# power.net
KiCad netlist of a schematic drawn in Altium Designer
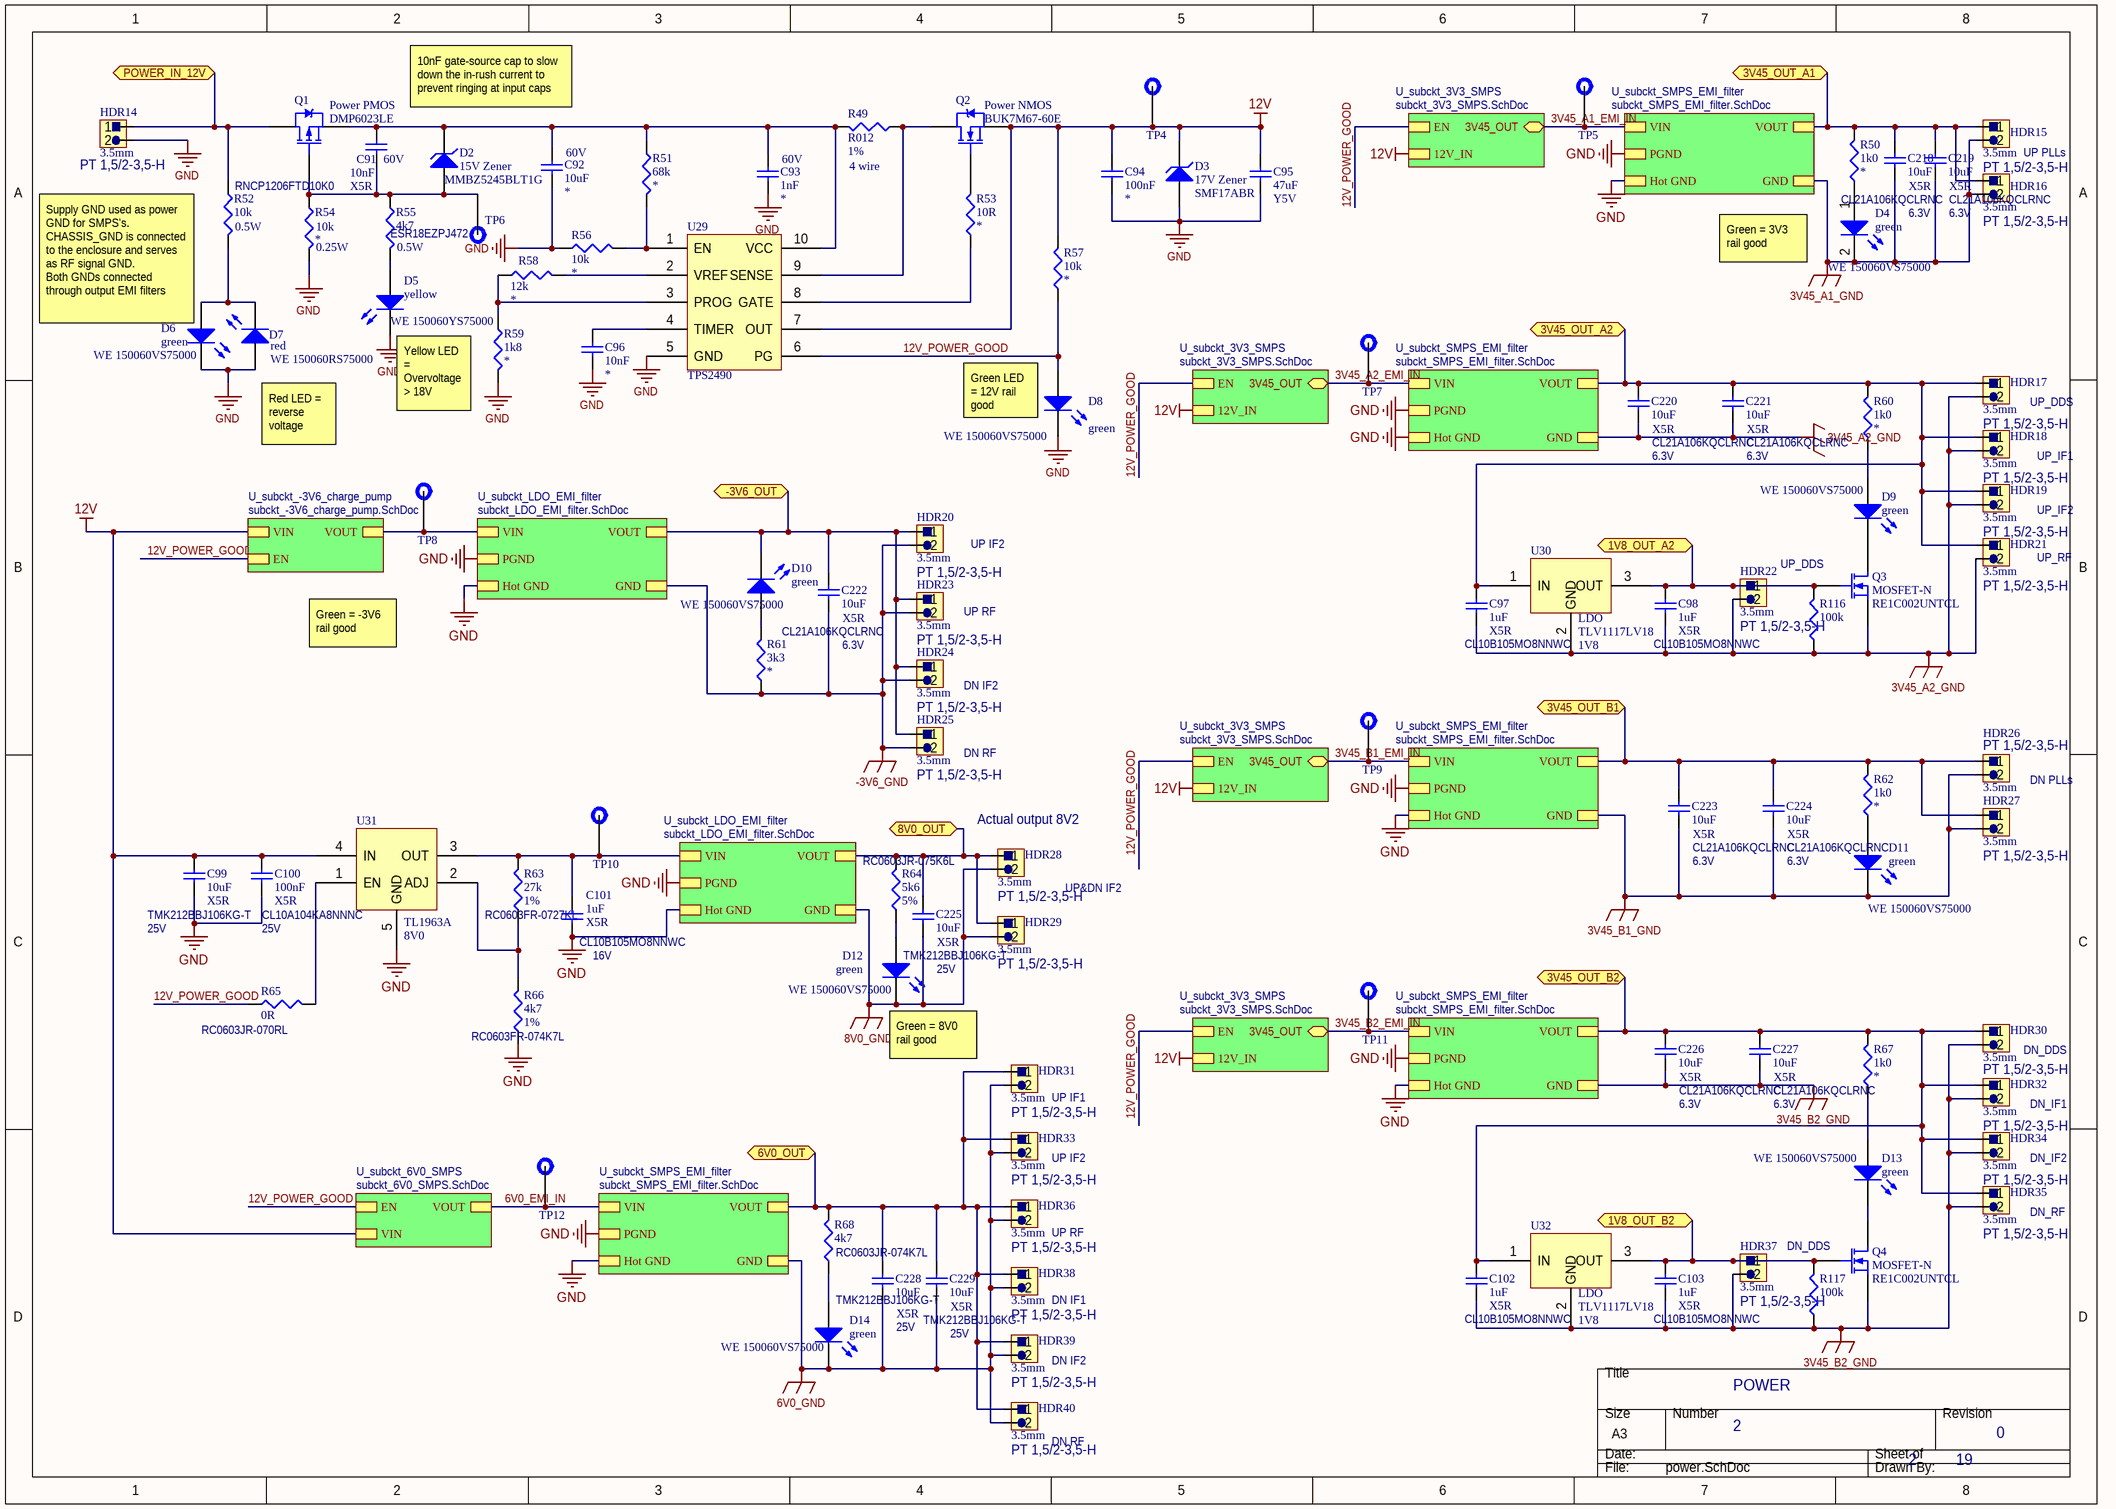
[diagram p0: power.SchDoc]

(export (version "E")
  (design (tool "Eeschema 10.0.6"))
  (components
    (comp (ref "C91")
      (value "60V")
      (footprint "TBD")
      (description "Capacitor")
      (fields (field (name "ALTIUM_VALUE") "10nF") (field (name "DIELECTRIC") "X5R"))
      (libsource (lib "lib_basic") (part "Capacitor"))
    )
    (comp (ref "C92")
      (value "60V")
      (footprint "TBD")
      (description "Capacitor")
      (fields (field (name "ALTIUM_VALUE") "10uF") (field (name "DIELECTRIC") "*"))
      (libsource (lib "lib_basic") (part "Capacitor"))
    )
    (comp (ref "C93")
      (value "60V")
      (footprint "TBD")
      (description "Capacitor")
      (fields (field (name "ALTIUM_VALUE") "1nF") (field (name "DIELECTRIC") "*"))
      (libsource (lib "lib_basic") (part "Capacitor"))
    )
    (comp (ref "C94")
      (value "100nF")
      (footprint "TBD")
      (description "Capacitor")
      (fields (field (name "DIELECTRIC") "*"))
      (libsource (lib "lib_basic") (part "Capacitor"))
    )
    (comp (ref "C95")
      (value "47uF")
      (footprint "TBD")
      (description "Capacitor")
      (fields (field (name "DIELECTRIC") "Y5V"))
      (libsource (lib "lib_basic") (part "Capacitor"))
    )
    (comp (ref "C96")
      (value "10nF")
      (footprint "TBD")
      (description "Capacitor")
      (fields (field (name "DIELECTRIC") "*"))
      (libsource (lib "lib_basic") (part "Capacitor"))
    )
    (comp (ref "C97")
      (value "1uF")
      (footprint "CAP0603")
      (description "Capacitor")
      (fields (field (name "DIELECTRIC") "X5R") (field (name "MODEL") "CL10B105MO8NNWC"))
      (libsource (lib "lib_basic") (part "Capacitor"))
    )
    (comp (ref "C98")
      (value "1uF")
      (footprint "CAP0603")
      (description "Capacitor")
      (fields (field (name "DIELECTRIC") "X5R") (field (name "MODEL") "CL10B105MO8NNWC"))
      (libsource (lib "lib_basic") (part "Capacitor"))
    )
    (comp (ref "C99")
      (value "10uF")
      (footprint "lib_basic:CAP0805")
      (description "Capacitor")
      (fields
        (field (name "DIELECTRIC") "X5R")
        (field (name "MODEL") "TMK212BBJ106KG-T")
        (field (name "VOLTAGE") "25V")
      )
      (libsource (lib "lib_basic") (part "Capacitor"))
    )
    (comp (ref "C100")
      (value "100nF")
      (footprint "CAP0603")
      (description "Capacitor")
      (fields
        (field (name "DIELECTRIC") "X5R")
        (field (name "MODEL") "CL10A104KA8NNNC")
        (field (name "VOLTAGE") "25V")
      )
      (libsource (lib "lib_basic") (part "Capacitor"))
    )
    (comp (ref "C101")
      (value "1uF")
      (footprint "CAP0603")
      (description "Capacitor")
      (fields
        (field (name "DIELECTRIC") "X5R")
        (field (name "MODEL") "CL10B105MO8NNWC")
        (field (name "VOLTAGE") "16V")
      )
      (libsource (lib "lib_basic") (part "Capacitor"))
    )
    (comp (ref "C102")
      (value "1uF")
      (footprint "CAP0603")
      (description "Capacitor")
      (fields (field (name "DIELECTRIC") "X5R") (field (name "MODEL") "CL10B105MO8NNWC"))
      (libsource (lib "lib_basic") (part "Capacitor"))
    )
    (comp (ref "C103")
      (value "1uF")
      (footprint "CAP0603")
      (description "Capacitor")
      (fields (field (name "DIELECTRIC") "X5R") (field (name "MODEL") "CL10B105MO8NNWC"))
      (libsource (lib "lib_basic") (part "Capacitor"))
    )
    (comp (ref "C218")
      (value "10uF")
      (footprint "lib_basic:CAP0805")
      (description "Capacitor")
      (fields
        (field (name "DIELECTRIC") "X5R")
        (field (name "MODEL") "CL21A106KQCLRNC")
        (field (name "VOLTAGE") "6.3V")
      )
      (libsource (lib "lib_basic") (part "Capacitor"))
    )
    (comp (ref "C219")
      (value "10uF")
      (footprint "lib_basic:CAP0805")
      (description "Capacitor")
      (fields
        (field (name "DIELECTRIC") "X5R")
        (field (name "MODEL") "CL21A106KQCLRNC")
        (field (name "VOLTAGE") "6.3V")
      )
      (libsource (lib "lib_basic") (part "Capacitor"))
    )
    (comp (ref "C220")
      (value "10uF")
      (footprint "lib_basic:CAP0805")
      (description "Capacitor")
      (fields
        (field (name "DIELECTRIC") "X5R")
        (field (name "MODEL") "CL21A106KQCLRNC")
        (field (name "VOLTAGE") "6.3V")
      )
      (libsource (lib "lib_basic") (part "Capacitor"))
    )
    (comp (ref "C221")
      (value "10uF")
      (footprint "lib_basic:CAP0805")
      (description "Capacitor")
      (fields
        (field (name "DIELECTRIC") "X5R")
        (field (name "MODEL") "CL21A106KQCLRNC")
        (field (name "VOLTAGE") "6.3V")
      )
      (libsource (lib "lib_basic") (part "Capacitor"))
    )
    (comp (ref "C222")
      (value "10uF")
      (footprint "lib_basic:CAP0805")
      (description "Capacitor")
      (fields
        (field (name "DIELECTRIC") "X5R")
        (field (name "MODEL") "CL21A106KQCLRNC")
        (field (name "VOLTAGE") "6.3V")
      )
      (libsource (lib "lib_basic") (part "Capacitor"))
    )
    (comp (ref "C223")
      (value "10uF")
      (footprint "lib_basic:CAP0805")
      (description "Capacitor")
      (fields
        (field (name "DIELECTRIC") "X5R")
        (field (name "MODEL") "CL21A106KQCLRNC")
        (field (name "VOLTAGE") "6.3V")
      )
      (libsource (lib "lib_basic") (part "Capacitor"))
    )
    (comp (ref "C224")
      (value "10uF")
      (footprint "lib_basic:CAP0805")
      (description "Capacitor")
      (fields
        (field (name "DIELECTRIC") "X5R")
        (field (name "MODEL") "CL21A106KQCLRNC")
        (field (name "VOLTAGE") "6.3V")
      )
      (libsource (lib "lib_basic") (part "Capacitor"))
    )
    (comp (ref "C225")
      (value "10uF")
      (footprint "lib_basic:CAP0805")
      (description "Capacitor")
      (fields
        (field (name "DIELECTRIC") "X5R")
        (field (name "MODEL") "TMK212BBJ106KG-T")
        (field (name "VOLTAGE") "25V")
      )
      (libsource (lib "lib_basic") (part "Capacitor"))
    )
    (comp (ref "C226")
      (value "10uF")
      (footprint "lib_basic:CAP0805")
      (description "Capacitor")
      (fields
        (field (name "DIELECTRIC") "X5R")
        (field (name "MODEL") "CL21A106KQCLRNC")
        (field (name "VOLTAGE") "6.3V")
      )
      (libsource (lib "lib_basic") (part "Capacitor"))
    )
    (comp (ref "C227")
      (value "10uF")
      (footprint "lib_basic:CAP0805")
      (description "Capacitor")
      (fields
        (field (name "DIELECTRIC") "X5R")
        (field (name "MODEL") "CL21A106KQCLRNC")
        (field (name "VOLTAGE") "6.3V")
      )
      (libsource (lib "lib_basic") (part "Capacitor"))
    )
    (comp (ref "C228")
      (value "10uF")
      (footprint "lib_basic:CAP0805")
      (description "Capacitor")
      (fields
        (field (name "DIELECTRIC") "X5R")
        (field (name "MODEL") "TMK212BBJ106KG-T")
        (field (name "VOLTAGE") "25V")
      )
      (libsource (lib "lib_basic") (part "Capacitor"))
    )
    (comp (ref "C229")
      (value "10uF")
      (footprint "lib_basic:CAP0805")
      (description "Capacitor")
      (fields
        (field (name "DIELECTRIC") "X5R")
        (field (name "MODEL") "TMK212BBJ106KG-T")
        (field (name "VOLTAGE") "25V")
      )
      (libsource (lib "lib_basic") (part "Capacitor"))
    )
    (comp (ref "D2")
      (value "15V Zener")
      (footprint "TBD")
      (description "Zener Diode")
      (fields (field (name "MODEL") "MMBZ5245BLT1G"))
      (libsource (lib "lib_basic") (part "D Zener"))
    )
    (comp (ref "D3")
      (value "17V Zener")
      (footprint "TBD")
      (description "Zener Diode")
      (fields (field (name "MODEL") "SMF17ABR"))
      (libsource (lib "lib_basic") (part "D Zener"))
    )
    (comp (ref "D4")
      (value "LED")
      (footprint "LED0603")
      (fields (field (name "COLOUR") "green") (field (name "MODEL") "WE 150060VS75000"))
      (libsource (lib "") (part "LED_1"))
    )
    (comp (ref "D5")
      (value "LED")
      (footprint "LED0603")
      (fields (field (name "COLOUR") "yellow") (field (name "MODEL") "WE 150060YS75000"))
      (libsource (lib "lib_basic") (part "LED"))
    )
    (comp (ref "D6")
      (value "LED")
      (footprint "LED0603")
      (fields (field (name "COLOUR") "green") (field (name "MODEL") "WE 150060VS75000"))
      (libsource (lib "lib_basic") (part "LED"))
    )
    (comp (ref "D7")
      (value "LED")
      (footprint "LED0603")
      (fields (field (name "COLOUR") "red") (field (name "MODEL") "WE 150060RS75000"))
      (libsource (lib "lib_basic") (part "LED"))
    )
    (comp (ref "D8")
      (value "LED")
      (footprint "LED0603")
      (fields (field (name "COLOUR") "green") (field (name "MODEL") "WE 150060VS75000"))
      (libsource (lib "lib_basic") (part "LED"))
    )
    (comp (ref "D9")
      (value "LED")
      (footprint "LED0603")
      (fields (field (name "COLOUR") "green") (field (name "MODEL") "WE 150060VS75000"))
      (libsource (lib "lib_basic") (part "LED"))
    )
    (comp (ref "D10")
      (value "LED")
      (footprint "LED0603")
      (fields (field (name "COLOUR") "green") (field (name "MODEL") "WE 150060VS75000"))
      (libsource (lib "lib_basic") (part "LED"))
    )
    (comp (ref "D11")
      (value "LED")
      (footprint "LED0603")
      (fields (field (name "COLOUR") "green") (field (name "MODEL") "WE 150060VS75000"))
      (libsource (lib "lib_basic") (part "LED"))
    )
    (comp (ref "D12")
      (value "LED")
      (footprint "LED0603")
      (fields (field (name "COLOUR") "green") (field (name "MODEL") "WE 150060VS75000"))
      (libsource (lib "lib_basic") (part "LED"))
    )
    (comp (ref "D13")
      (value "LED")
      (footprint "LED0603")
      (fields (field (name "COLOUR") "green") (field (name "MODEL") "WE 150060VS75000"))
      (libsource (lib "lib_basic") (part "LED"))
    )
    (comp (ref "D14")
      (value "LED")
      (footprint "LED0603")
      (fields (field (name "COLOUR") "green") (field (name "MODEL") "WE 150060VS75000"))
      (libsource (lib "lib_basic") (part "LED"))
    )
    (comp (ref "HDR14")
      (value "Header 2 pins")
      (footprint "lib_connectors:2X 3.5mm TH screw terminal - interlock")
      (fields (field (name "PITCH") "3.5mm") (field (name "MODEL") "PT 1,5/2-3,5-H"))
      (libsource (lib "") (part "Header2_1"))
    )
    (comp (ref "HDR15")
      (value "Header 2 pins")
      (footprint "lib_connectors:2X 3.5mm TH screw terminal - interlock")
      (fields (field (name "PITCH") "3.5mm") (field (name "MODEL") "PT 1,5/2-3,5-H"))
      (libsource (lib "lib_Connectors") (part "Header2"))
    )
    (comp (ref "HDR16")
      (value "Header 2 pins")
      (footprint "lib_connectors:2X 3.5mm TH screw terminal - interlock")
      (fields (field (name "PITCH") "3.5mm") (field (name "MODEL") "PT 1,5/2-3,5-H"))
      (libsource (lib "lib_Connectors") (part "Header2"))
    )
    (comp (ref "HDR17")
      (value "Header 2 pins")
      (footprint "lib_connectors:2X 3.5mm TH screw terminal - interlock")
      (fields (field (name "PITCH") "3.5mm") (field (name "MODEL") "PT 1,5/2-3,5-H"))
      (libsource (lib "lib_Connectors") (part "Header2"))
    )
    (comp (ref "HDR18")
      (value "Header 2 pins")
      (footprint "lib_connectors:2X 3.5mm TH screw terminal - interlock")
      (fields (field (name "PITCH") "3.5mm") (field (name "MODEL") "PT 1,5/2-3,5-H"))
      (libsource (lib "lib_Connectors") (part "Header2"))
    )
    (comp (ref "HDR19")
      (value "Header 2 pins")
      (footprint "lib_connectors:2X 3.5mm TH screw terminal - interlock")
      (fields (field (name "PITCH") "3.5mm") (field (name "MODEL") "PT 1,5/2-3,5-H"))
      (libsource (lib "lib_Connectors") (part "Header2"))
    )
    (comp (ref "HDR20")
      (value "Header 2 pins")
      (footprint "lib_connectors:2X 3.5mm TH screw terminal - interlock")
      (fields (field (name "PITCH") "3.5mm") (field (name "MODEL") "PT 1,5/2-3,5-H"))
      (libsource (lib "lib_Connectors") (part "Header2"))
    )
    (comp (ref "HDR21")
      (value "Header 2 pins")
      (footprint "lib_connectors:2X 3.5mm TH screw terminal - interlock")
      (fields (field (name "PITCH") "3.5mm") (field (name "MODEL") "PT 1,5/2-3,5-H"))
      (libsource (lib "lib_Connectors") (part "Header2"))
    )
    (comp (ref "HDR22")
      (value "Header 2 pins")
      (footprint "lib_connectors:2X 3.5mm TH screw terminal - interlock")
      (fields (field (name "PITCH") "3.5mm") (field (name "MODEL") "PT 1,5/2-3,5-H"))
      (libsource (lib "lib_Connectors") (part "Header2"))
    )
    (comp (ref "HDR23")
      (value "Header 2 pins")
      (footprint "lib_connectors:2X 3.5mm TH screw terminal - interlock")
      (fields (field (name "PITCH") "3.5mm") (field (name "MODEL") "PT 1,5/2-3,5-H"))
      (libsource (lib "lib_Connectors") (part "Header2"))
    )
    (comp (ref "HDR24")
      (value "Header 2 pins")
      (footprint "lib_connectors:2X 3.5mm TH screw terminal - interlock")
      (fields (field (name "PITCH") "3.5mm") (field (name "MODEL") "PT 1,5/2-3,5-H"))
      (libsource (lib "lib_Connectors") (part "Header2"))
    )
    (comp (ref "HDR25")
      (value "Header 2 pins")
      (footprint "lib_connectors:2X 3.5mm TH screw terminal - interlock")
      (fields (field (name "PITCH") "3.5mm") (field (name "MODEL") "PT 1,5/2-3,5-H"))
      (libsource (lib "lib_Connectors") (part "Header2"))
    )
    (comp (ref "HDR26")
      (value "Header 2 pins")
      (footprint "lib_connectors:2X 3.5mm TH screw terminal - interlock")
      (fields (field (name "PITCH") "3.5mm") (field (name "MODEL") "PT 1,5/2-3,5-H"))
      (libsource (lib "lib_Connectors") (part "Header2"))
    )
    (comp (ref "HDR27")
      (value "Header 2 pins")
      (footprint "lib_connectors:2X 3.5mm TH screw terminal - interlock")
      (fields (field (name "PITCH") "3.5mm") (field (name "MODEL") "PT 1,5/2-3,5-H"))
      (libsource (lib "lib_Connectors") (part "Header2"))
    )
    (comp (ref "HDR28")
      (value "Header 2 pins")
      (footprint "lib_connectors:2X 3.5mm TH screw terminal - interlock")
      (fields (field (name "PITCH") "3.5mm") (field (name "MODEL") "PT 1,5/2-3,5-H"))
      (libsource (lib "lib_Connectors") (part "Header2"))
    )
    (comp (ref "HDR29")
      (value "Header 2 pins")
      (footprint "lib_connectors:2X 3.5mm TH screw terminal - interlock")
      (fields (field (name "PITCH") "3.5mm") (field (name "MODEL") "PT 1,5/2-3,5-H"))
      (libsource (lib "lib_Connectors") (part "Header2"))
    )
    (comp (ref "HDR30")
      (value "Header 2 pins")
      (footprint "lib_connectors:2X 3.5mm TH screw terminal - interlock")
      (fields (field (name "PITCH") "3.5mm") (field (name "MODEL") "PT 1,5/2-3,5-H"))
      (libsource (lib "lib_Connectors") (part "Header2"))
    )
    (comp (ref "HDR31")
      (value "Header 2 pins")
      (footprint "lib_connectors:2X 3.5mm TH screw terminal - interlock")
      (fields (field (name "PITCH") "3.5mm") (field (name "MODEL") "PT 1,5/2-3,5-H"))
      (libsource (lib "lib_Connectors") (part "Header2"))
    )
    (comp (ref "HDR32")
      (value "Header 2 pins")
      (footprint "lib_connectors:2X 3.5mm TH screw terminal - interlock")
      (fields (field (name "PITCH") "3.5mm") (field (name "MODEL") "PT 1,5/2-3,5-H"))
      (libsource (lib "lib_Connectors") (part "Header2"))
    )
    (comp (ref "HDR33")
      (value "Header 2 pins")
      (footprint "lib_connectors:2X 3.5mm TH screw terminal - interlock")
      (fields (field (name "PITCH") "3.5mm") (field (name "MODEL") "PT 1,5/2-3,5-H"))
      (libsource (lib "lib_Connectors") (part "Header2"))
    )
    (comp (ref "HDR34")
      (value "Header 2 pins")
      (footprint "lib_connectors:2X 3.5mm TH screw terminal - interlock")
      (fields (field (name "PITCH") "3.5mm") (field (name "MODEL") "PT 1,5/2-3,5-H"))
      (libsource (lib "lib_Connectors") (part "Header2"))
    )
    (comp (ref "HDR35")
      (value "Header 2 pins")
      (footprint "lib_connectors:2X 3.5mm TH screw terminal - interlock")
      (fields (field (name "PITCH") "3.5mm") (field (name "MODEL") "PT 1,5/2-3,5-H"))
      (libsource (lib "lib_Connectors") (part "Header2"))
    )
    (comp (ref "HDR36")
      (value "Header 2 pins")
      (footprint "lib_connectors:2X 3.5mm TH screw terminal - interlock")
      (fields (field (name "PITCH") "3.5mm") (field (name "MODEL") "PT 1,5/2-3,5-H"))
      (libsource (lib "lib_Connectors") (part "Header2"))
    )
    (comp (ref "HDR37")
      (value "Header 2 pins")
      (footprint "lib_connectors:2X 3.5mm TH screw terminal - interlock")
      (fields (field (name "PITCH") "3.5mm") (field (name "MODEL") "PT 1,5/2-3,5-H"))
      (libsource (lib "lib_Connectors") (part "Header2"))
    )
    (comp (ref "HDR38")
      (value "Header 2 pins")
      (footprint "lib_connectors:2X 3.5mm TH screw terminal - interlock")
      (fields (field (name "PITCH") "3.5mm") (field (name "MODEL") "PT 1,5/2-3,5-H"))
      (libsource (lib "lib_Connectors") (part "Header2"))
    )
    (comp (ref "HDR39")
      (value "Header 2 pins")
      (footprint "lib_connectors:2X 3.5mm TH screw terminal - interlock")
      (fields (field (name "PITCH") "3.5mm") (field (name "MODEL") "PT 1,5/2-3,5-H"))
      (libsource (lib "lib_Connectors") (part "Header2"))
    )
    (comp (ref "HDR40")
      (value "Header 2 pins")
      (footprint "lib_connectors:2X 3.5mm TH screw terminal - interlock")
      (fields (field (name "PITCH") "3.5mm") (field (name "MODEL") "PT 1,5/2-3,5-H"))
      (libsource (lib "lib_Connectors") (part "Header2"))
    )
    (comp (ref "Q1")
      (value "Power PMOS")
      (description "P-Channel Power MOSFET")
      (fields (field (name "MODEL") "DMP6023LE"))
      (libsource (lib "lib_basic") (part "Power PMOS"))
    )
    (comp (ref "Q2")
      (value "Power NMOS")
      (footprint "TBD")
      (description "N-Channel Power MOSFET")
      (fields (field (name "MODEL") "BUK7M67-60E"))
      (libsource (lib "lib_basic") (part "Power NMOS"))
    )
    (comp (ref "Q3")
      (value "MOSFET-N")
      (footprint "lib_basic:SC89 3 leads")
      (description "N-Channel MOSFET")
      (fields (field (name "MODEL") "RE1C002UNTCL"))
      (libsource (lib "lib_basic") (part "MOSFET-N"))
    )
    (comp (ref "Q4")
      (value "MOSFET-N")
      (footprint "lib_basic:SC89 3 leads")
      (description "N-Channel MOSFET")
      (fields (field (name "MODEL") "RE1C002UNTCL"))
      (libsource (lib "lib_basic") (part "MOSFET-N"))
    )
    (comp (ref "R49")
      (value "4 wire")
      (footprint "TBD")
      (description "Resistor")
      (fields (field (name "ALTIUM_VALUE") "R012") (field (name "TYPE") "1%"))
      (libsource (lib "lib_basic") (part "Resistor"))
    )
    (comp (ref "R50")
      (value "1k0")
      (footprint "RES0603")
      (description "Resistor")
      (fields (field (name "TYPE") "*"))
      (libsource (lib "lib_basic") (part "Resistor"))
    )
    (comp (ref "R51")
      (value "68k")
      (footprint "TBD")
      (description "Resistor")
      (fields (field (name "TYPE") "*"))
      (libsource (lib "lib_basic") (part "Resistor"))
    )
    (comp (ref "R52")
      (value "0.5W")
      (footprint "lib_basic:RES1206")
      (description "Resistor")
      (fields (field (name "ALTIUM_VALUE") "10k") (field (name "MODEL") "RNCP1206FTD10K0"))
      (libsource (lib "lib_basic") (part "Resistor"))
    )
    (comp (ref "R53")
      (value "10R")
      (footprint "TBD")
      (description "Resistor")
      (fields (field (name "TYPE") "*"))
      (libsource (lib "lib_basic") (part "Resistor"))
    )
    (comp (ref "R54")
      (value "0.25W")
      (footprint "TBD")
      (description "Resistor")
      (fields (field (name "ALTIUM_VALUE") "10k") (field (name "TYPE") "*"))
      (libsource (lib "lib_basic") (part "Resistor"))
    )
    (comp (ref "R55")
      (value "0.5W")
      (footprint "lib_basic:RES1206")
      (description "Resistor")
      (fields (field (name "ALTIUM_VALUE") "4k7") (field (name "MODEL") "ESR18EZPJ472"))
      (libsource (lib "lib_basic") (part "Resistor"))
    )
    (comp (ref "R56")
      (value "10k")
      (footprint "TBD")
      (description "Resistor")
      (fields (field (name "TYPE") "*"))
      (libsource (lib "lib_basic") (part "Resistor"))
    )
    (comp (ref "R57")
      (value "10k")
      (footprint "TBD")
      (description "Resistor")
      (fields (field (name "TYPE") "*"))
      (libsource (lib "lib_basic") (part "Resistor"))
    )
    (comp (ref "R58")
      (value "12k")
      (footprint "TBD")
      (description "Resistor")
      (fields (field (name "TYPE") "*"))
      (libsource (lib "lib_basic") (part "Resistor"))
    )
    (comp (ref "R59")
      (value "1k8")
      (footprint "TBD")
      (description "Resistor")
      (fields (field (name "TYPE") "*"))
      (libsource (lib "lib_basic") (part "Resistor"))
    )
    (comp (ref "R60")
      (value "1k0")
      (footprint "RES0603")
      (description "Resistor")
      (fields (field (name "TYPE") "*"))
      (libsource (lib "lib_basic") (part "Resistor"))
    )
    (comp (ref "R61")
      (value "3k3")
      (footprint "RES0603")
      (description "Resistor")
      (fields (field (name "TYPE") "*"))
      (libsource (lib "lib_basic") (part "Resistor"))
    )
    (comp (ref "R62")
      (value "1k0")
      (footprint "RES0603")
      (description "Resistor")
      (fields (field (name "TYPE") "*"))
      (libsource (lib "lib_basic") (part "Resistor"))
    )
    (comp (ref "R63")
      (value "27k")
      (footprint "RES0603")
      (description "Resistor")
      (fields (field (name "TYPE") "1%") (field (name "MODEL") "RC0603FR-0727KL"))
      (libsource (lib "lib_basic") (part "Resistor"))
    )
    (comp (ref "R64")
      (value "5k6")
      (footprint "RES0603")
      (description "Resistor")
      (fields (field (name "TYPE") "5%") (field (name "MODEL") "RC0603JR-075K6L"))
      (libsource (lib "lib_basic") (part "Resistor"))
    )
    (comp (ref "R65")
      (value "0R")
      (footprint "RES0603")
      (description "Resistor")
      (fields (field (name "MODEL") "RC0603JR-070RL"))
      (libsource (lib "lib_basic") (part "Resistor"))
    )
    (comp (ref "R66")
      (value "4k7")
      (footprint "RES0603")
      (description "Resistor")
      (fields (field (name "TYPE") "1%") (field (name "MODEL") "RC0603FR-074K7L"))
      (libsource (lib "lib_basic") (part "Resistor"))
    )
    (comp (ref "R67")
      (value "1k0")
      (footprint "RES0603")
      (description "Resistor")
      (fields (field (name "TYPE") "*"))
      (libsource (lib "lib_basic") (part "Resistor"))
    )
    (comp (ref "R68")
      (value "4k7")
      (footprint "RES0603")
      (description "Resistor")
      (fields (field (name "MODEL") "RC0603JR-074K7L"))
      (libsource (lib "lib_basic") (part "Resistor"))
    )
    (comp (ref "R116")
      (value "100k")
      (footprint "RES0603")
      (description "Resistor")
      (libsource (lib "lib_basic") (part "Resistor"))
    )
    (comp (ref "R117")
      (value "100k")
      (footprint "RES0603")
      (description "Resistor")
      (libsource (lib "lib_basic") (part "Resistor"))
    )
    (comp (ref "TP4")
      (value "Test point")
      (footprint "lib_connectors:1XHeader 100mil")
      (libsource (lib "lib_basic") (part "Test point"))
    )
    (comp (ref "TP5")
      (value "Test point")
      (footprint "lib_connectors:1XHeader 100mil")
      (libsource (lib "lib_basic") (part "Test point"))
    )
    (comp (ref "TP6")
      (value "Test point")
      (footprint "lib_connectors:1XHeader 100mil")
      (libsource (lib "lib_basic") (part "Test point"))
    )
    (comp (ref "TP7")
      (value "Test point")
      (footprint "lib_connectors:1XHeader 100mil")
      (libsource (lib "lib_basic") (part "Test point"))
    )
    (comp (ref "TP8")
      (value "Test point")
      (footprint "lib_connectors:1XHeader 100mil")
      (libsource (lib "lib_basic") (part "Test point"))
    )
    (comp (ref "TP9")
      (value "Test point")
      (footprint "lib_connectors:1XHeader 100mil")
      (libsource (lib "lib_basic") (part "Test point"))
    )
    (comp (ref "TP10")
      (value "Test point")
      (footprint "lib_connectors:1XHeader 100mil")
      (libsource (lib "lib_basic") (part "Test point"))
    )
    (comp (ref "TP11")
      (value "Test point")
      (footprint "lib_connectors:1XHeader 100mil")
      (libsource (lib "lib_basic") (part "Test point"))
    )
    (comp (ref "TP12")
      (value "Test point")
      (footprint "lib_connectors:1XHeader 100mil")
      (libsource (lib "lib_basic") (part "Test point"))
    )
    (comp (ref "U29")
      (value "TPS2490")
      (footprint "TBD")
      (description "High voltage hot swap controller")
      (libsource (lib "lib_TI_Power") (part "TPS2490"))
    )
    (comp (ref "U30")
      (value "LDO")
      (footprint "lib_basic:SOT223 (4)")
      (description "LDO w/o EN")
      (fields (field (name "MODEL") "TLV1117LV18") (field (name "VOLTAGE") "1V8"))
      (libsource (lib "lib_TI_Power") (part "LDO_no_EN"))
    )
    (comp (ref "U31")
      (value "LDO")
      (footprint "lib_basic:SOT223 (6)")
      (description "Adjustable LDO")
      (fields (field (name "MODEL") "TL1963A") (field (name "VOLTAGE") "8V0"))
      (libsource (lib "lib_TI_Power") (part "LDO_Adj"))
    )
    (comp (ref "U32")
      (value "LDO")
      (footprint "lib_basic:SOT223 (4)")
      (description "LDO w/o EN")
      (fields (field (name "MODEL") "TLV1117LV18") (field (name "VOLTAGE") "1V8"))
      (libsource (lib "lib_TI_Power") (part "LDO_no_EN"))
    )
  )
  (nets
    (net (code "1") (name "-3V6_GND") (class "Default")
      (node (ref "C222") (pin "1") (pinfunction "1_1") (pintype "passive"))
      (node (ref "HDR20") (pin "2") (pinfunction "2_2") (pintype "passive"))
      (node (ref "HDR23") (pin "2") (pinfunction "2_2") (pintype "passive"))
      (node (ref "HDR24") (pin "2") (pinfunction "2_2") (pintype "passive"))
      (node (ref "HDR25") (pin "2") (pinfunction "2_2") (pintype "passive"))
      (node (ref "R61") (pin "2") (pinfunction "2_2") (pintype "passive"))
    )
    (net (code "2") (name "/-3V6_OUT") (class "Default")
      (node (ref "C222") (pin "2") (pinfunction "2_2") (pintype "passive"))
      (node (ref "D10") (pin "2") (pinfunction "K_2") (pintype "passive"))
      (node (ref "HDR20") (pin "1") (pinfunction "1_1") (pintype "passive"))
      (node (ref "HDR23") (pin "1") (pinfunction "1_1") (pintype "passive"))
      (node (ref "HDR24") (pin "1") (pinfunction "1_1") (pintype "passive"))
      (node (ref "HDR25") (pin "1") (pinfunction "1_1") (pintype "passive"))
    )
    (net (code "3") (name "/1V8_OUT_A2") (class "Default")
      (node (ref "C98") (pin "2") (pinfunction "2_2") (pintype "passive"))
      (node (ref "HDR22") (pin "1") (pinfunction "1_1") (pintype "passive"))
      (node (ref "Q3") (pin "2") (pinfunction "G_2") (pintype "passive"))
      (node (ref "R116") (pin "2") (pinfunction "2_2") (pintype "passive"))
      (node (ref "U30") (pin "3") (pinfunction "OUT_3") (pintype "power_in"))
    )
    (net (code "4") (name "/1V8_OUT_B2") (class "Default")
      (node (ref "C103") (pin "2") (pinfunction "2_2") (pintype "passive"))
      (node (ref "HDR37") (pin "1") (pinfunction "1_1") (pintype "passive"))
      (node (ref "Q4") (pin "2") (pinfunction "G_2") (pintype "passive"))
      (node (ref "R117") (pin "2") (pinfunction "2_2") (pintype "passive"))
      (node (ref "U32") (pin "3") (pinfunction "OUT_3") (pintype "power_in"))
    )
    (net (code "5") (name "/3V45_A1_EMI_IN") (class "Default")
      (node (ref "TP5") (pin "1") (pinfunction "1_1") (pintype "passive"))
    )
    (net (code "6") (name "/3V45_A2_EMI_IN") (class "Default")
      (node (ref "TP7") (pin "1") (pinfunction "1_1") (pintype "passive"))
    )
    (net (code "7") (name "/3V45_B1_EMI_IN") (class "Default")
      (node (ref "TP9") (pin "1") (pinfunction "1_1") (pintype "passive"))
    )
    (net (code "8") (name "/3V45_B2_EMI_IN") (class "Default")
      (node (ref "TP11") (pin "1") (pinfunction "1_1") (pintype "passive"))
    )
    (net (code "9") (name "/3V45_OUT_A1") (class "Default")
      (node (ref "C218") (pin "2") (pinfunction "2_2") (pintype "passive"))
      (node (ref "C219") (pin "2") (pinfunction "2_2") (pintype "passive"))
      (node (ref "HDR15") (pin "1") (pinfunction "1_1") (pintype "passive"))
      (node (ref "HDR16") (pin "1") (pinfunction "1_1") (pintype "passive"))
      (node (ref "R50") (pin "2") (pinfunction "2_2") (pintype "passive"))
    )
    (net (code "10") (name "/3V45_OUT_A2") (class "Default")
      (node (ref "C220") (pin "2") (pinfunction "2_2") (pintype "passive"))
      (node (ref "C221") (pin "2") (pinfunction "2_2") (pintype "passive"))
      (node (ref "C97") (pin "2") (pinfunction "2_2") (pintype "passive"))
      (node (ref "HDR17") (pin "1") (pinfunction "1_1") (pintype "passive"))
      (node (ref "HDR18") (pin "1") (pinfunction "1_1") (pintype "passive"))
      (node (ref "HDR19") (pin "1") (pinfunction "1_1") (pintype "passive"))
      (node (ref "HDR21") (pin "1") (pinfunction "1_1") (pintype "passive"))
      (node (ref "R60") (pin "2") (pinfunction "2_2") (pintype "passive"))
      (node (ref "U30") (pin "1") (pinfunction "IN_1") (pintype "power_in"))
    )
    (net (code "11") (name "/3V45_OUT_B1") (class "Default")
      (node (ref "C223") (pin "2") (pinfunction "2_2") (pintype "passive"))
      (node (ref "C224") (pin "2") (pinfunction "2_2") (pintype "passive"))
      (node (ref "HDR26") (pin "1") (pinfunction "1_1") (pintype "passive"))
      (node (ref "HDR27") (pin "1") (pinfunction "1_1") (pintype "passive"))
      (node (ref "R62") (pin "2") (pinfunction "2_2") (pintype "passive"))
    )
    (net (code "12") (name "/3V45_OUT_B2") (class "Default")
      (node (ref "C102") (pin "2") (pinfunction "2_2") (pintype "passive"))
      (node (ref "C226") (pin "2") (pinfunction "2_2") (pintype "passive"))
      (node (ref "C227") (pin "2") (pinfunction "2_2") (pintype "passive"))
      (node (ref "HDR30") (pin "1") (pinfunction "1_1") (pintype "passive"))
      (node (ref "HDR32") (pin "1") (pinfunction "1_1") (pintype "passive"))
      (node (ref "HDR34") (pin "1") (pinfunction "1_1") (pintype "passive"))
      (node (ref "HDR35") (pin "1") (pinfunction "1_1") (pintype "passive"))
      (node (ref "R67") (pin "2") (pinfunction "2_2") (pintype "passive"))
      (node (ref "U32") (pin "1") (pinfunction "IN_1") (pintype "power_in"))
    )
    (net (code "13") (name "/6V0_EMI_IN") (class "Default")
      (node (ref "TP12") (pin "1") (pinfunction "1_1") (pintype "passive"))
    )
    (net (code "14") (name "/6V0_OUT") (class "Default")
      (node (ref "C228") (pin "2") (pinfunction "2_2") (pintype "passive"))
      (node (ref "C229") (pin "2") (pinfunction "2_2") (pintype "passive"))
      (node (ref "HDR31") (pin "1") (pinfunction "1_1") (pintype "passive"))
      (node (ref "HDR33") (pin "1") (pinfunction "1_1") (pintype "passive"))
      (node (ref "HDR36") (pin "1") (pinfunction "1_1") (pintype "passive"))
      (node (ref "HDR38") (pin "1") (pinfunction "1_1") (pintype "passive"))
      (node (ref "HDR39") (pin "1") (pinfunction "1_1") (pintype "passive"))
      (node (ref "HDR40") (pin "1") (pinfunction "1_1") (pintype "passive"))
      (node (ref "R68") (pin "2") (pinfunction "2_2") (pintype "passive"))
    )
    (net (code "15") (name "/8V0_OUT") (class "Default")
      (node (ref "C225") (pin "2") (pinfunction "2_2") (pintype "passive"))
      (node (ref "HDR28") (pin "1") (pinfunction "1_1") (pintype "passive"))
      (node (ref "HDR29") (pin "1") (pinfunction "1_1") (pintype "passive"))
      (node (ref "R64") (pin "2") (pinfunction "2_2") (pintype "passive"))
    )
    (net (code "16") (name "/12V_POWER_GOOD") (class "Default")
      (node (ref "D8") (pin "1") (pinfunction "A_1") (pintype "passive"))
      (node (ref "R57") (pin "1") (pinfunction "1_1") (pintype "passive"))
      (node (ref "R65") (pin "1") (pinfunction "1_1") (pintype "passive"))
      (node (ref "U29") (pin "6") (pinfunction "PG_6") (pintype "passive"))
    )
    (net (code "17") (name "/POWER_IN_12V") (class "Default")
      (node (ref "HDR14") (pin "1") (pinfunction "1_1") (pintype "passive"))
      (node (ref "Q1") (pin "2") (pinfunction "D_2") (pintype "passive"))
      (node (ref "R52") (pin "1") (pinfunction "1_1") (pintype "passive"))
    )
    (net (code "18") (name "/VIN") (class "Default")
      (node (ref "TP8") (pin "1") (pinfunction "1_1") (pintype "passive"))
    )
    (net (code "19") (name "/VIN_1") (class "Default")
      (node (ref "C101") (pin "2") (pinfunction "2_2") (pintype "passive"))
      (node (ref "R63") (pin "2") (pinfunction "2_2") (pintype "passive"))
      (node (ref "TP10") (pin "1") (pinfunction "1_1") (pintype "passive"))
      (node (ref "U31") (pin "3") (pinfunction "OUT_3") (pintype "passive"))
    )
    (net (code "20") (name "3V45_A1_GND") (class "Default")
      (node (ref "C218") (pin "1") (pinfunction "1_1") (pintype "passive"))
      (node (ref "C219") (pin "1") (pinfunction "1_1") (pintype "passive"))
      (node (ref "D4") (pin "2") (pinfunction "K_2") (pintype "passive"))
      (node (ref "HDR15") (pin "2") (pinfunction "2_2") (pintype "passive"))
      (node (ref "HDR16") (pin "2") (pinfunction "2_2") (pintype "passive"))
    )
    (net (code "21") (name "3V45_A2_GND") (class "Default")
      (node (ref "C220") (pin "1") (pinfunction "1_1") (pintype "passive"))
      (node (ref "C221") (pin "1") (pinfunction "1_1") (pintype "passive"))
      (node (ref "C97") (pin "1") (pinfunction "1_1") (pintype "passive"))
      (node (ref "C98") (pin "1") (pinfunction "1_1") (pintype "passive"))
      (node (ref "HDR17") (pin "2") (pinfunction "2_2") (pintype "passive"))
      (node (ref "HDR18") (pin "2") (pinfunction "2_2") (pintype "passive"))
      (node (ref "HDR19") (pin "2") (pinfunction "2_2") (pintype "passive"))
      (node (ref "HDR21") (pin "2") (pinfunction "2_2") (pintype "passive"))
      (node (ref "HDR22") (pin "2") (pinfunction "2_2") (pintype "passive"))
      (node (ref "Q3") (pin "3") (pinfunction "S_3") (pintype "passive"))
      (node (ref "R116") (pin "1") (pinfunction "1_1") (pintype "passive"))
      (node (ref "U30") (pin "2") (pinfunction "GND_2") (pintype "power_in"))
    )
    (net (code "22") (name "3V45_B1_GND") (class "Default")
      (node (ref "C223") (pin "1") (pinfunction "1_1") (pintype "passive"))
      (node (ref "C224") (pin "1") (pinfunction "1_1") (pintype "passive"))
      (node (ref "D11") (pin "2") (pinfunction "K_2") (pintype "passive"))
      (node (ref "HDR26") (pin "2") (pinfunction "2_2") (pintype "passive"))
      (node (ref "HDR27") (pin "2") (pinfunction "2_2") (pintype "passive"))
    )
    (net (code "23") (name "3V45_B2_GND") (class "Default")
      (node (ref "C102") (pin "1") (pinfunction "1_1") (pintype "passive"))
      (node (ref "C103") (pin "1") (pinfunction "1_1") (pintype "passive"))
      (node (ref "C226") (pin "1") (pinfunction "1_1") (pintype "passive"))
      (node (ref "C227") (pin "1") (pinfunction "1_1") (pintype "passive"))
      (node (ref "HDR30") (pin "2") (pinfunction "2_2") (pintype "passive"))
      (node (ref "HDR32") (pin "2") (pinfunction "2_2") (pintype "passive"))
      (node (ref "HDR34") (pin "2") (pinfunction "2_2") (pintype "passive"))
      (node (ref "HDR35") (pin "2") (pinfunction "2_2") (pintype "passive"))
      (node (ref "HDR37") (pin "2") (pinfunction "2_2") (pintype "passive"))
      (node (ref "Q4") (pin "3") (pinfunction "S_3") (pintype "passive"))
      (node (ref "R117") (pin "1") (pinfunction "1_1") (pintype "passive"))
      (node (ref "U32") (pin "2") (pinfunction "GND_2") (pintype "power_in"))
    )
    (net (code "24") (name "6V0_GND") (class "Default")
      (node (ref "C228") (pin "1") (pinfunction "1_1") (pintype "passive"))
      (node (ref "C229") (pin "1") (pinfunction "1_1") (pintype "passive"))
      (node (ref "D14") (pin "2") (pinfunction "K_2") (pintype "passive"))
      (node (ref "HDR31") (pin "2") (pinfunction "2_2") (pintype "passive"))
      (node (ref "HDR33") (pin "2") (pinfunction "2_2") (pintype "passive"))
      (node (ref "HDR36") (pin "2") (pinfunction "2_2") (pintype "passive"))
      (node (ref "HDR38") (pin "2") (pinfunction "2_2") (pintype "passive"))
      (node (ref "HDR39") (pin "2") (pinfunction "2_2") (pintype "passive"))
      (node (ref "HDR40") (pin "2") (pinfunction "2_2") (pintype "passive"))
    )
    (net (code "25") (name "8V0_GND") (class "Default")
      (node (ref "C225") (pin "1") (pinfunction "1_1") (pintype "passive"))
      (node (ref "D12") (pin "2") (pinfunction "K_2") (pintype "passive"))
      (node (ref "HDR28") (pin "2") (pinfunction "2_2") (pintype "passive"))
      (node (ref "HDR29") (pin "2") (pinfunction "2_2") (pintype "passive"))
    )
    (net (code "26") (name "12V") (class "Default")
      (node (ref "C100") (pin "2") (pinfunction "2_2") (pintype "passive"))
      (node (ref "C94") (pin "1") (pinfunction "1_1") (pintype "passive"))
      (node (ref "C95") (pin "2") (pinfunction "2_2") (pintype "passive"))
      (node (ref "C99") (pin "2") (pinfunction "2_2") (pintype "passive"))
      (node (ref "D3") (pin "2") (pinfunction "K_2") (pintype "passive"))
      (node (ref "Q2") (pin "3") (pinfunction "S_3") (pintype "passive"))
      (node (ref "R57") (pin "2") (pinfunction "2_2") (pintype "passive"))
      (node (ref "TP4") (pin "1") (pinfunction "1_1") (pintype "passive"))
      (node (ref "U29") (pin "7") (pinfunction "OUT_7") (pintype "passive"))
      (node (ref "U31") (pin "4") (pinfunction "IN_4") (pintype "passive"))
    )
    (net (code "27") (name "GND") (class "Default")
      (node (ref "C100") (pin "1") (pinfunction "1_1") (pintype "passive"))
      (node (ref "C101") (pin "1") (pinfunction "1_1") (pintype "passive"))
      (node (ref "C92") (pin "2") (pinfunction "2_2") (pintype "passive"))
      (node (ref "C93") (pin "2") (pinfunction "2_2") (pintype "passive"))
      (node (ref "C94") (pin "2") (pinfunction "2_2") (pintype "passive"))
      (node (ref "C95") (pin "1") (pinfunction "1_1") (pintype "passive"))
      (node (ref "C96") (pin "2") (pinfunction "2_2") (pintype "passive"))
      (node (ref "C99") (pin "1") (pinfunction "1_1") (pintype "passive"))
      (node (ref "D3") (pin "1") (pinfunction "A_1") (pintype "passive"))
      (node (ref "D5") (pin "2") (pinfunction "K_2") (pintype "passive"))
      (node (ref "D6") (pin "2") (pinfunction "K_2") (pintype "passive"))
      (node (ref "D7") (pin "1") (pinfunction "A_1") (pintype "passive"))
      (node (ref "D8") (pin "2") (pinfunction "K_2") (pintype "passive"))
      (node (ref "HDR14") (pin "2") (pinfunction "2_2") (pintype "passive"))
      (node (ref "R54") (pin "2") (pinfunction "2_2") (pintype "passive"))
      (node (ref "R56") (pin "1") (pinfunction "1_1") (pintype "passive"))
      (node (ref "R59") (pin "2") (pinfunction "2_2") (pintype "passive"))
      (node (ref "R66") (pin "1") (pinfunction "1_1") (pintype "passive"))
      (node (ref "U29") (pin "5") (pinfunction "GND_5") (pintype "passive"))
      (node (ref "U31") (pin "5") (pinfunction "GND_5") (pintype "power_in"))
    )
    (net (code "28") (name "Net-(D2-A)") (class "Default")
      (node (ref "C91") (pin "2") (pinfunction "2_2") (pintype "passive"))
      (node (ref "D2") (pin "1") (pinfunction "A_1") (pintype "passive"))
      (node (ref "Q1") (pin "1") (pinfunction "G_1") (pintype "passive"))
      (node (ref "R54") (pin "1") (pinfunction "1_1") (pintype "passive"))
      (node (ref "R55") (pin "1") (pinfunction "1_1") (pintype "passive"))
      (node (ref "TP6") (pin "1") (pinfunction "1_1") (pintype "passive"))
    )
    (net (code "29") (name "Net-(D2-K)") (class "Default")
      (node (ref "C91") (pin "1") (pinfunction "1_1") (pintype "passive"))
      (node (ref "C92") (pin "1") (pinfunction "1_1") (pintype "passive"))
      (node (ref "C93") (pin "1") (pinfunction "1_1") (pintype "passive"))
      (node (ref "D2") (pin "2") (pinfunction "K_2") (pintype "passive"))
      (node (ref "Q1") (pin "3") (pinfunction "S_3") (pintype "passive"))
      (node (ref "R49") (pin "2") (pinfunction "2_2") (pintype "passive"))
      (node (ref "R51") (pin "1") (pinfunction "1_1") (pintype "passive"))
      (node (ref "U29") (pin "10") (pinfunction "VCC_10") (pintype "passive"))
    )
    (net (code "30") (name "Net-(D4-A)") (class "Default")
      (node (ref "D4") (pin "1") (pinfunction "A_1") (pintype "passive"))
      (node (ref "R50") (pin "1") (pinfunction "1_1") (pintype "passive"))
    )
    (net (code "31") (name "Net-(D5-A)") (class "Default")
      (node (ref "D5") (pin "1") (pinfunction "A_1") (pintype "passive"))
      (node (ref "R55") (pin "2") (pinfunction "2_2") (pintype "passive"))
    )
    (net (code "32") (name "Net-(D6-A)") (class "Default")
      (node (ref "D6") (pin "1") (pinfunction "A_1") (pintype "passive"))
      (node (ref "D7") (pin "2") (pinfunction "K_2") (pintype "passive"))
      (node (ref "R52") (pin "2") (pinfunction "2_2") (pintype "passive"))
    )
    (net (code "33") (name "Net-(D9-A)") (class "Default")
      (node (ref "D9") (pin "1") (pinfunction "A_1") (pintype "passive"))
      (node (ref "R60") (pin "1") (pinfunction "1_1") (pintype "passive"))
    )
    (net (code "34") (name "Net-(D9-K)") (class "Default")
      (node (ref "D9") (pin "2") (pinfunction "K_2") (pintype "passive"))
      (node (ref "Q3") (pin "1") (pinfunction "D_1") (pintype "passive"))
    )
    (net (code "35") (name "Net-(D10-A)") (class "Default")
      (node (ref "D10") (pin "1") (pinfunction "A_1") (pintype "passive"))
      (node (ref "R61") (pin "1") (pinfunction "1_1") (pintype "passive"))
    )
    (net (code "36") (name "Net-(D11-A)") (class "Default")
      (node (ref "D11") (pin "1") (pinfunction "A_1") (pintype "passive"))
      (node (ref "R62") (pin "1") (pinfunction "1_1") (pintype "passive"))
    )
    (net (code "37") (name "Net-(D12-A)") (class "Default")
      (node (ref "D12") (pin "1") (pinfunction "A_1") (pintype "passive"))
      (node (ref "R64") (pin "1") (pinfunction "1_1") (pintype "passive"))
    )
    (net (code "38") (name "Net-(D13-A)") (class "Default")
      (node (ref "D13") (pin "1") (pinfunction "A_1") (pintype "passive"))
      (node (ref "R67") (pin "1") (pinfunction "1_1") (pintype "passive"))
    )
    (net (code "39") (name "Net-(D13-K)") (class "Default")
      (node (ref "D13") (pin "2") (pinfunction "K_2") (pintype "passive"))
      (node (ref "Q4") (pin "1") (pinfunction "D_1") (pintype "passive"))
    )
    (net (code "40") (name "Net-(D14-A)") (class "Default")
      (node (ref "D14") (pin "1") (pinfunction "A_1") (pintype "passive"))
      (node (ref "R68") (pin "1") (pinfunction "1_1") (pintype "passive"))
    )
    (net (code "41") (name "Net-(Q2-D)") (class "Default")
      (node (ref "Q2") (pin "2") (pinfunction "D_2") (pintype "passive"))
      (node (ref "R49") (pin "1") (pinfunction "1_1") (pintype "passive"))
      (node (ref "U29") (pin "9") (pinfunction "SENSE_9") (pintype "passive"))
    )
    (net (code "42") (name "Net-(Q2-G)") (class "Default")
      (node (ref "Q2") (pin "1") (pinfunction "G_1") (pintype "passive"))
      (node (ref "R53") (pin "2") (pinfunction "2_2") (pintype "passive"))
    )
    (net (code "43") (name "Net-(U29-EN)") (class "Default")
      (node (ref "R51") (pin "2") (pinfunction "2_2") (pintype "passive"))
      (node (ref "R56") (pin "2") (pinfunction "2_2") (pintype "passive"))
      (node (ref "U29") (pin "1") (pinfunction "EN_1") (pintype "passive"))
    )
    (net (code "44") (name "Net-(U29-GATE)") (class "Default")
      (node (ref "R53") (pin "1") (pinfunction "1_1") (pintype "passive"))
      (node (ref "U29") (pin "8") (pinfunction "GATE_8") (pintype "passive"))
    )
    (net (code "45") (name "Net-(U29-PROG)") (class "Default")
      (node (ref "R58") (pin "1") (pinfunction "1_1") (pintype "passive"))
      (node (ref "R59") (pin "1") (pinfunction "1_1") (pintype "passive"))
      (node (ref "U29") (pin "3") (pinfunction "PROG_3") (pintype "passive"))
    )
    (net (code "46") (name "Net-(U29-TIMER)") (class "Default")
      (node (ref "C96") (pin "1") (pinfunction "1_1") (pintype "passive"))
      (node (ref "U29") (pin "4") (pinfunction "TIMER_4") (pintype "passive"))
    )
    (net (code "47") (name "Net-(U29-VREF)") (class "Default")
      (node (ref "R58") (pin "2") (pinfunction "2_2") (pintype "passive"))
      (node (ref "U29") (pin "2") (pinfunction "VREF_2") (pintype "passive"))
    )
    (net (code "48") (name "Net-(U31-ADJ)") (class "Default")
      (node (ref "R63") (pin "1") (pinfunction "1_1") (pintype "passive"))
      (node (ref "R66") (pin "2") (pinfunction "2_2") (pintype "passive"))
      (node (ref "U31") (pin "2") (pinfunction "ADJ_2") (pintype "power_in"))
    )
    (net (code "49") (name "Net-(U31-EN)") (class "Default")
      (node (ref "R65") (pin "2") (pinfunction "2_2") (pintype "passive"))
      (node (ref "U31") (pin "1") (pinfunction "EN_1") (pintype "power_in"))
    )
  )
)
